# INTERFACE.net
KiCad netlist of a schematic drawn in Altium Designer
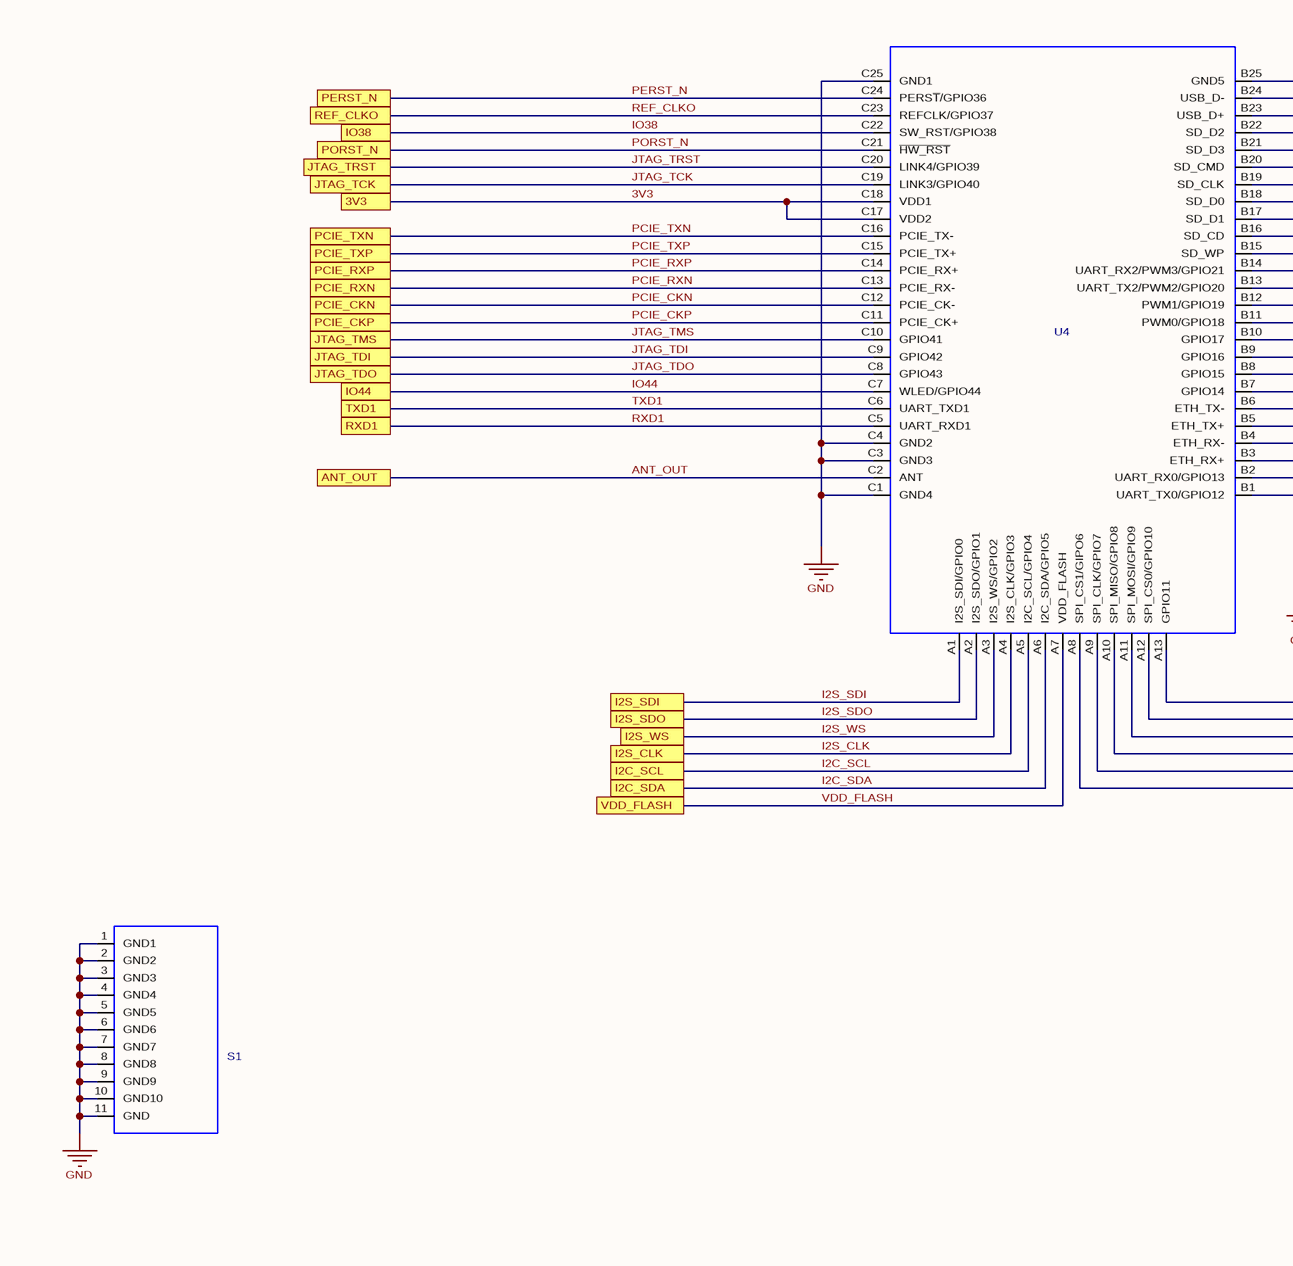
[diagram p0: INTERFACE.SchDoc, left]
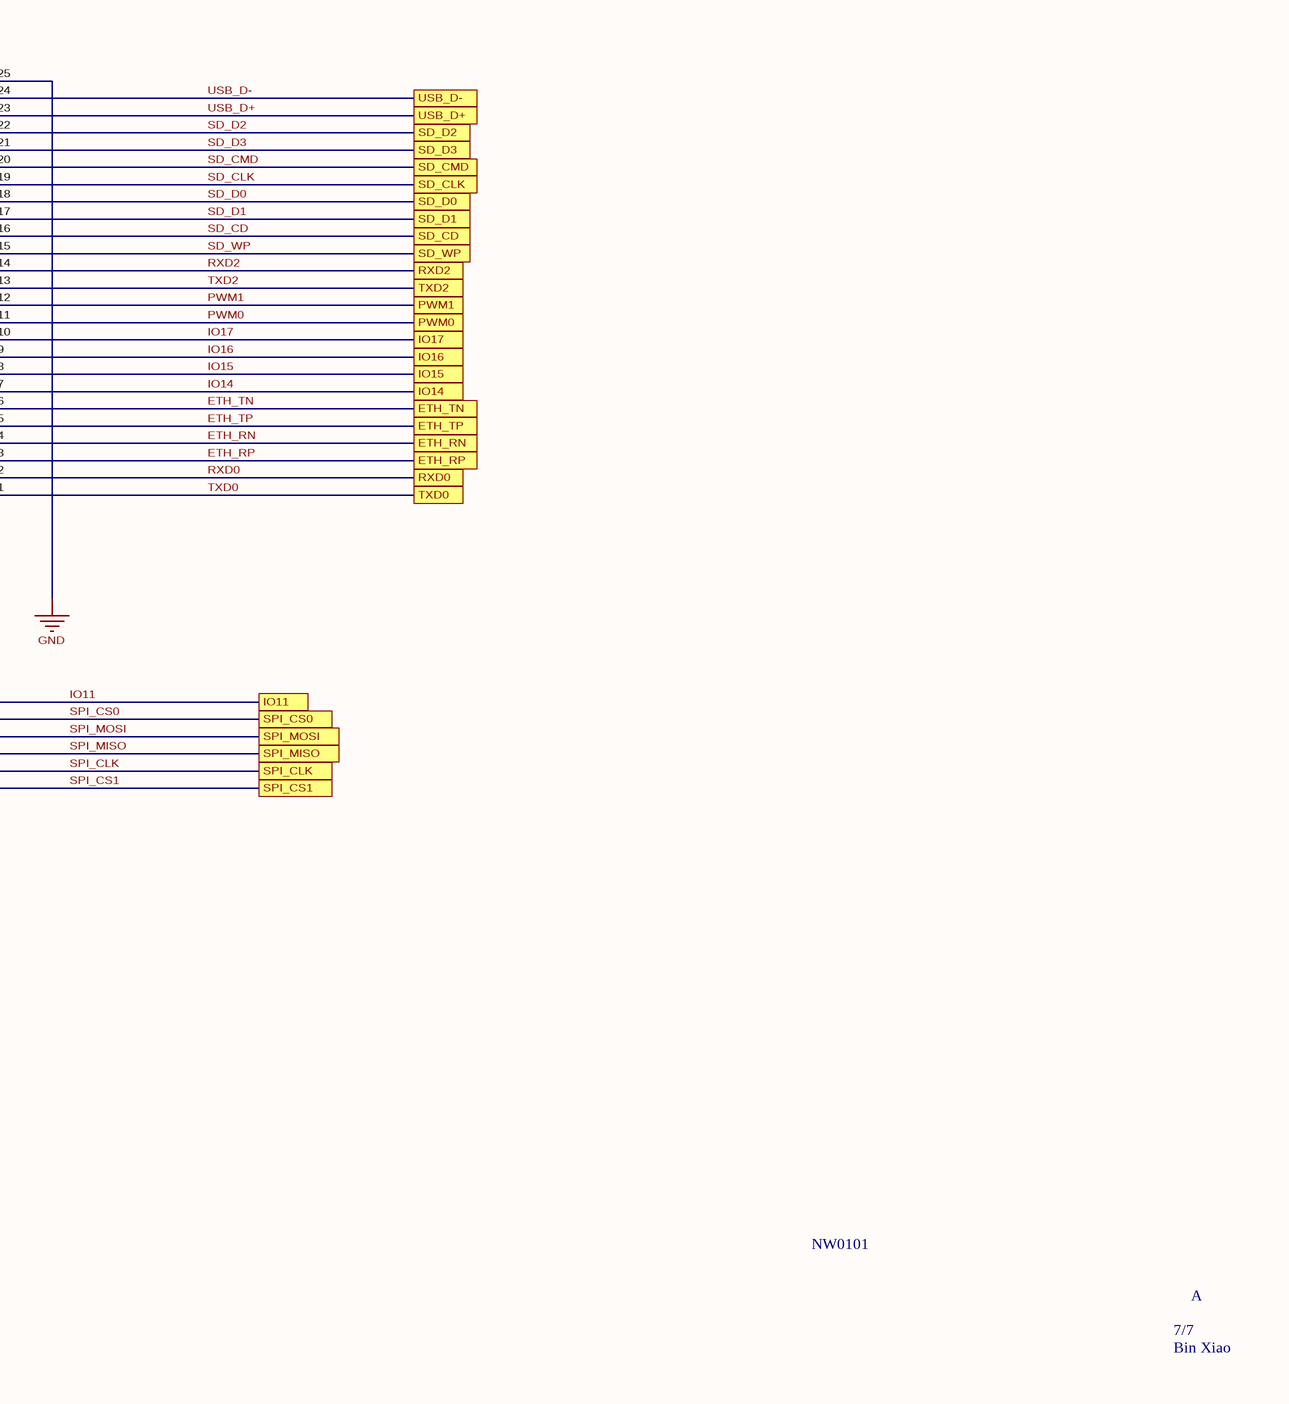
[diagram p1: INTERFACE.SchDoc, right]

(export (version "E")
  (design (tool "Eeschema 10.0.6"))
  (components
    (comp (ref "S1")
      (value "O2S-SHIELD")
      (footprint "O2S-SHIELD")
      (description "O2S SHIELD")
      (fields (field (name "MANUFACTURER") "RYSE Inc."))
      (libsource (lib "*") (part "O2S-SHIELD"))
    )
    (comp (ref "U4")
      (value "OMEGA2S-PCB")
      (footprint "OMEGA2S+PCB")
      (description "RX TXRX MODULE WIFI U.FL SMD")
      (fields (field (name "MANUFACTURER") "Onion Corporation") (field (name "PART NUMBER") "OM-O2S"))
      (libsource (lib "*") (part "OMEGA2S-PCB"))
    )
  )
  (nets
    (net (code "1") (name "/3V3") (class "Default")
      (node (ref "U4") (pin "C17") (pinfunction "VDD2_C17") (pintype "passive"))
      (node (ref "U4") (pin "C18") (pinfunction "VDD1_C18") (pintype "passive"))
    )
    (net (code "2") (name "/ANT_OUT") (class "Default")
      (node (ref "U4") (pin "C2") (pinfunction "ANT_C2") (pintype "passive"))
    )
    (net (code "3") (name "/ETH_RN") (class "Default")
      (node (ref "U4") (pin "B4") (pinfunction "ETH_RX-_B4") (pintype "passive"))
    )
    (net (code "4") (name "/ETH_RP") (class "Default")
      (node (ref "U4") (pin "B3") (pinfunction "ETH_RX+_B3") (pintype "passive"))
    )
    (net (code "5") (name "/ETH_TN") (class "Default")
      (node (ref "U4") (pin "B6") (pinfunction "ETH_TX-_B6") (pintype "passive"))
    )
    (net (code "6") (name "/ETH_TP") (class "Default")
      (node (ref "U4") (pin "B5") (pinfunction "ETH_TX+_B5") (pintype "passive"))
    )
    (net (code "7") (name "/I2C_SCL") (class "Default")
      (node (ref "U4") (pin "A5") (pinfunction "I2C_SCL/GPIO4_A5") (pintype "passive"))
    )
    (net (code "8") (name "/I2C_SDA") (class "Default")
      (node (ref "U4") (pin "A6") (pinfunction "I2C_SDA/GPIO5_A6") (pintype "passive"))
    )
    (net (code "9") (name "/I2S_CLK") (class "Default")
      (node (ref "U4") (pin "A4") (pinfunction "I2S_CLK/GPIO3_A4") (pintype "passive"))
    )
    (net (code "10") (name "/I2S_SDI") (class "Default")
      (node (ref "U4") (pin "A1") (pinfunction "I2S_SDI/GPIO0_A1") (pintype "passive"))
    )
    (net (code "11") (name "/I2S_SDO") (class "Default")
      (node (ref "U4") (pin "A2") (pinfunction "I2S_SDO/GPIO1_A2") (pintype "passive"))
    )
    (net (code "12") (name "/I2S_WS") (class "Default")
      (node (ref "U4") (pin "A3") (pinfunction "I2S_WS/GPIO2_A3") (pintype "passive"))
    )
    (net (code "13") (name "/IO11") (class "Default")
      (node (ref "U4") (pin "A13") (pinfunction "GPIO11_A13") (pintype "passive"))
    )
    (net (code "14") (name "/IO14") (class "Default")
      (node (ref "U4") (pin "B7") (pinfunction "GPIO14_B7") (pintype "passive"))
    )
    (net (code "15") (name "/IO15") (class "Default")
      (node (ref "U4") (pin "B8") (pinfunction "GPIO15_B8") (pintype "passive"))
    )
    (net (code "16") (name "/IO16") (class "Default")
      (node (ref "U4") (pin "B9") (pinfunction "GPIO16_B9") (pintype "passive"))
    )
    (net (code "17") (name "/IO17") (class "Default")
      (node (ref "U4") (pin "B10") (pinfunction "GPIO17_B10") (pintype "passive"))
    )
    (net (code "18") (name "/IO38") (class "Default")
      (node (ref "U4") (pin "C22") (pinfunction "SW_RST/GPIO38_C22") (pintype "passive"))
    )
    (net (code "19") (name "/IO44") (class "Default")
      (node (ref "U4") (pin "C7") (pinfunction "WLED/GPIO44_C7") (pintype "passive"))
    )
    (net (code "20") (name "/JTAG_TCK") (class "Default")
      (node (ref "U4") (pin "C19") (pinfunction "LINK3/GPIO40_C19") (pintype "passive"))
    )
    (net (code "21") (name "/JTAG_TDI") (class "Default")
      (node (ref "U4") (pin "C9") (pinfunction "GPIO42_C9") (pintype "passive"))
    )
    (net (code "22") (name "/JTAG_TDO") (class "Default")
      (node (ref "U4") (pin "C8") (pinfunction "GPIO43_C8") (pintype "passive"))
    )
    (net (code "23") (name "/JTAG_TMS") (class "Default")
      (node (ref "U4") (pin "C10") (pinfunction "GPIO41_C10") (pintype "passive"))
    )
    (net (code "24") (name "/JTAG_TRST") (class "Default")
      (node (ref "U4") (pin "C20") (pinfunction "LINK4/GPIO39_C20") (pintype "passive"))
    )
    (net (code "25") (name "/PCIE_CKN") (class "Default")
      (node (ref "U4") (pin "C12") (pinfunction "PCIE_CK-_C12") (pintype "passive"))
    )
    (net (code "26") (name "/PCIE_CKP") (class "Default")
      (node (ref "U4") (pin "C11") (pinfunction "PCIE_CK+_C11") (pintype "passive"))
    )
    (net (code "27") (name "/PCIE_RXN") (class "Default")
      (node (ref "U4") (pin "C13") (pinfunction "PCIE_RX-_C13") (pintype "passive"))
    )
    (net (code "28") (name "/PCIE_RXP") (class "Default")
      (node (ref "U4") (pin "C14") (pinfunction "PCIE_RX+_C14") (pintype "passive"))
    )
    (net (code "29") (name "/PCIE_TXN") (class "Default")
      (node (ref "U4") (pin "C16") (pinfunction "PCIE_TX-_C16") (pintype "passive"))
    )
    (net (code "30") (name "/PCIE_TXP") (class "Default")
      (node (ref "U4") (pin "C15") (pinfunction "PCIE_TX+_C15") (pintype "passive"))
    )
    (net (code "31") (name "/PERST_N") (class "Default")
      (node (ref "U4") (pin "C24") (pinfunction "PERS~{T}/GPIO36_C24") (pintype "passive"))
    )
    (net (code "32") (name "/PORST_N") (class "Default")
      (node (ref "U4") (pin "C21") (pinfunction "HW_RST_C21") (pintype "passive"))
    )
    (net (code "33") (name "/PWM0") (class "Default")
      (node (ref "U4") (pin "B11") (pinfunction "PWM0/GPIO18_B11") (pintype "passive"))
    )
    (net (code "34") (name "/PWM1") (class "Default")
      (node (ref "U4") (pin "B12") (pinfunction "PWM1/GPIO19_B12") (pintype "passive"))
    )
    (net (code "35") (name "/REF_CLKO") (class "Default")
      (node (ref "U4") (pin "C23") (pinfunction "REFCLK/GPIO37_C23") (pintype "passive"))
    )
    (net (code "36") (name "/RXD0") (class "Default")
      (node (ref "U4") (pin "B2") (pinfunction "UART_RX0/GPIO13_B2") (pintype "passive"))
    )
    (net (code "37") (name "/RXD1") (class "Default")
      (node (ref "U4") (pin "C5") (pinfunction "UART_RXD1_C5") (pintype "passive"))
    )
    (net (code "38") (name "/RXD2") (class "Default")
      (node (ref "U4") (pin "B14") (pinfunction "UART_RX2/PWM3/GPIO21_B14") (pintype "passive"))
    )
    (net (code "39") (name "/SD_CD") (class "Default")
      (node (ref "U4") (pin "B16") (pinfunction "SD_CD_B16") (pintype "passive"))
    )
    (net (code "40") (name "/SD_CLK") (class "Default")
      (node (ref "U4") (pin "B19") (pinfunction "SD_CLK_B19") (pintype "passive"))
    )
    (net (code "41") (name "/SD_CMD") (class "Default")
      (node (ref "U4") (pin "B20") (pinfunction "SD_CMD_B20") (pintype "passive"))
    )
    (net (code "42") (name "/SD_D0") (class "Default")
      (node (ref "U4") (pin "B18") (pinfunction "SD_D0_B18") (pintype "passive"))
    )
    (net (code "43") (name "/SD_D1") (class "Default")
      (node (ref "U4") (pin "B17") (pinfunction "SD_D1_B17") (pintype "passive"))
    )
    (net (code "44") (name "/SD_D2") (class "Default")
      (node (ref "U4") (pin "B22") (pinfunction "SD_D2_B22") (pintype "passive"))
    )
    (net (code "45") (name "/SD_D3") (class "Default")
      (node (ref "U4") (pin "B21") (pinfunction "SD_D3_B21") (pintype "passive"))
    )
    (net (code "46") (name "/SD_WP") (class "Default")
      (node (ref "U4") (pin "B15") (pinfunction "SD_WP_B15") (pintype "passive"))
    )
    (net (code "47") (name "/SPI_CLK") (class "Default")
      (node (ref "U4") (pin "A9") (pinfunction "SPI_CLK/GPIO7_A9") (pintype "passive"))
    )
    (net (code "48") (name "/SPI_CS0") (class "Default")
      (node (ref "U4") (pin "A12") (pinfunction "SPI_CS0/GPIO10_A12") (pintype "passive"))
    )
    (net (code "49") (name "/SPI_CS1") (class "Default")
      (node (ref "U4") (pin "A8") (pinfunction "SPI_CS1/GIPO6_A8") (pintype "passive"))
    )
    (net (code "50") (name "/SPI_MISO") (class "Default")
      (node (ref "U4") (pin "A10") (pinfunction "SPI_MISO/GPIO8_A10") (pintype "passive"))
    )
    (net (code "51") (name "/SPI_MOSI") (class "Default")
      (node (ref "U4") (pin "A11") (pinfunction "SPI_MOSI/GPIO9_A11") (pintype "passive"))
    )
    (net (code "52") (name "/TXD0") (class "Default")
      (node (ref "U4") (pin "B1") (pinfunction "UART_TX0/GPIO12_B1") (pintype "passive"))
    )
    (net (code "53") (name "/TXD1") (class "Default")
      (node (ref "U4") (pin "C6") (pinfunction "UART_TXD1_C6") (pintype "passive"))
    )
    (net (code "54") (name "/TXD2") (class "Default")
      (node (ref "U4") (pin "B13") (pinfunction "UART_TX2/PWM2/GPIO20_B13") (pintype "passive"))
    )
    (net (code "55") (name "/USB_D+") (class "Default")
      (node (ref "U4") (pin "B23") (pinfunction "USB_D+_B23") (pintype "passive"))
    )
    (net (code "56") (name "/USB_D-") (class "Default")
      (node (ref "U4") (pin "B24") (pinfunction "USB_D-_B24") (pintype "passive"))
    )
    (net (code "57") (name "/VDD_FLASH") (class "Default")
      (node (ref "U4") (pin "A7") (pinfunction "VDD_FLASH_A7") (pintype "passive"))
    )
    (net (code "58") (name "GND") (class "Default")
      (node (ref "S1") (pin "1") (pinfunction "GND1_1") (pintype "passive"))
      (node (ref "S1") (pin "10") (pinfunction "GND10_10") (pintype "passive"))
      (node (ref "S1") (pin "11") (pinfunction "GND_11") (pintype "passive"))
      (node (ref "S1") (pin "2") (pinfunction "GND2_2") (pintype "passive"))
      (node (ref "S1") (pin "3") (pinfunction "GND3_3") (pintype "passive"))
      (node (ref "S1") (pin "4") (pinfunction "GND4_4") (pintype "passive"))
      (node (ref "S1") (pin "5") (pinfunction "GND5_5") (pintype "passive"))
      (node (ref "S1") (pin "6") (pinfunction "GND6_6") (pintype "passive"))
      (node (ref "S1") (pin "7") (pinfunction "GND7_7") (pintype "passive"))
      (node (ref "S1") (pin "8") (pinfunction "GND8_8") (pintype "passive"))
      (node (ref "S1") (pin "9") (pinfunction "GND9_9") (pintype "passive"))
      (node (ref "U4") (pin "B25") (pinfunction "GND5_B25") (pintype "passive"))
      (node (ref "U4") (pin "C1") (pinfunction "GND4_C1") (pintype "passive"))
      (node (ref "U4") (pin "C25") (pinfunction "GND1_C25") (pintype "passive"))
      (node (ref "U4") (pin "C3") (pinfunction "GND3_C3") (pintype "passive"))
      (node (ref "U4") (pin "C4") (pinfunction "GND2_C4") (pintype "passive"))
    )
  )
)
